# MCU025A_AltRouting_Misc.net
KiCad netlist of a schematic drawn in Altium Designer
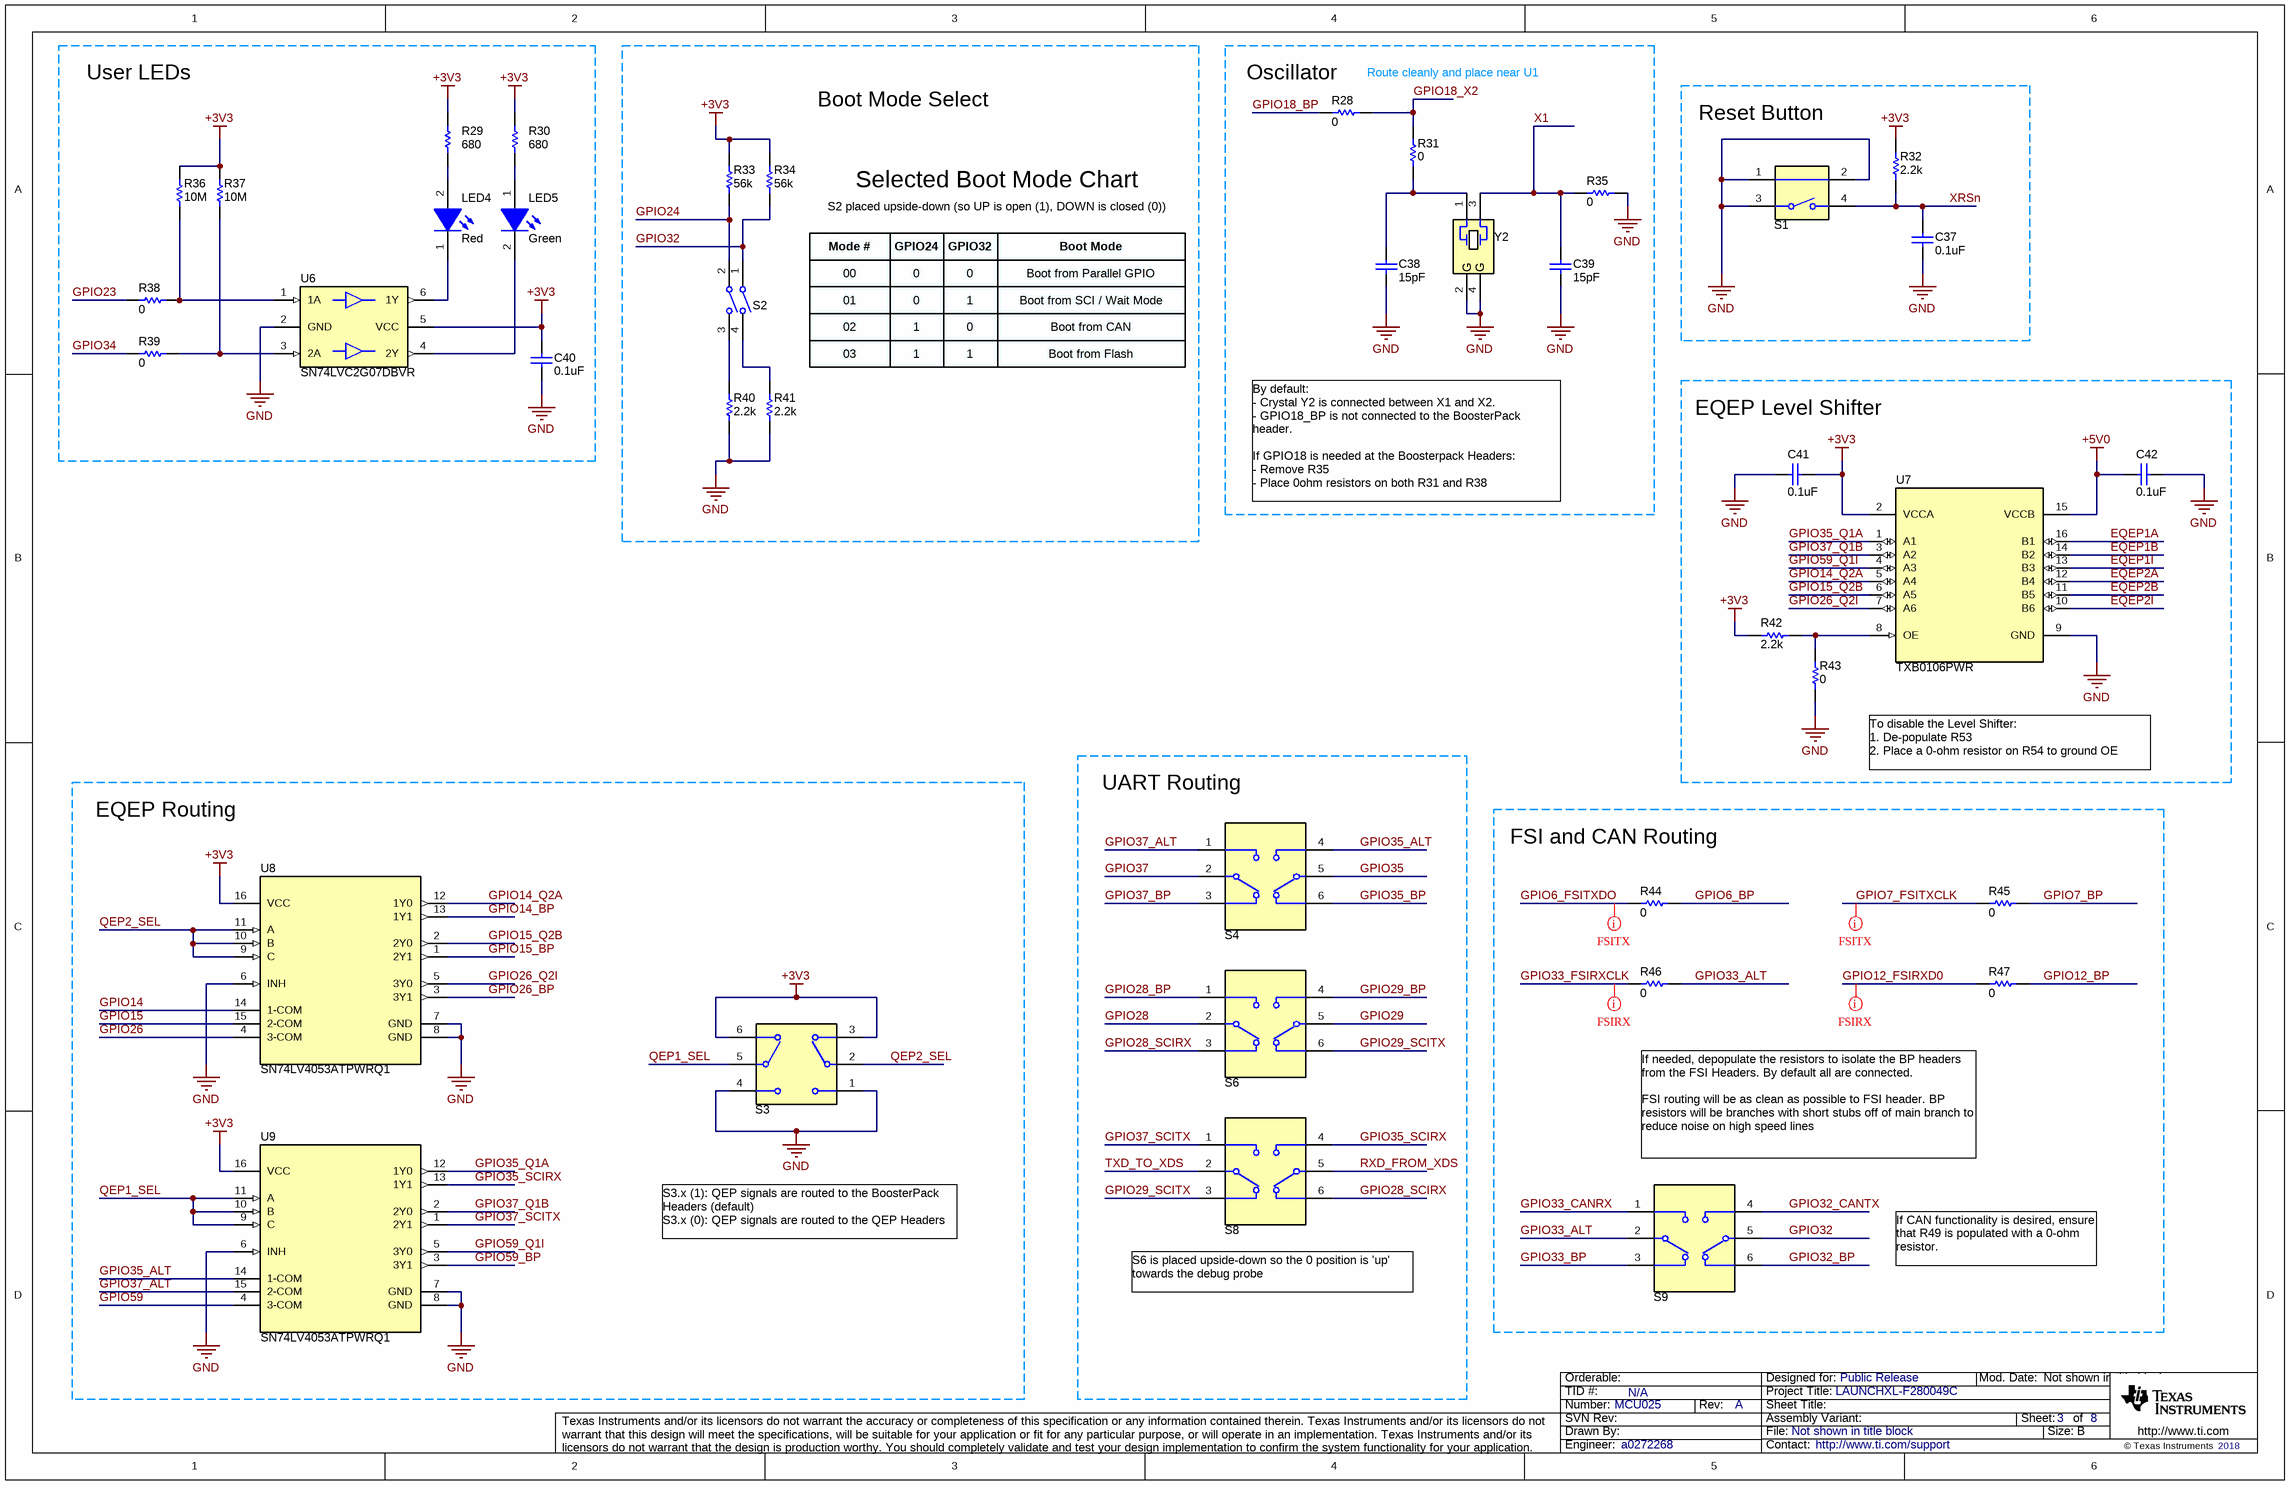
[diagram p0: MCU025A_AltRouting_Misc.SchDoc]

(export (version "E")
  (design (tool "Eeschema 10.0.6"))
  (components
    (comp (ref "C37")
      (value "GRM155R71A104KA01D")
      (footprint "0402")
      (description "CAP, CERM, 0.1 uF, 10 V, +/- 10%, X7R, 0402")
      (fields
        (field (name "VALUEDISPLAYED") "0.1uF")
        (field (name "MANUFACTURER") "MuRata")
        (field (name "PUBLISHER") "Texas Instruments")
      )
      (libsource (lib "Altium Vault - TI") (part "Capacitor"))
    )
    (comp (ref "C38")
      (value "GRM1555C1H150JA01D")
      (footprint "0402")
      (description "CAP, CERM, 15 pF, 50 V, +/- 5%, C0G/NP0, 0402")
      (fields
        (field (name "VALUEDISPLAYED") "15pF")
        (field (name "MANUFACTURER") "MuRata")
        (field (name "PUBLISHER") "Texas Instruments")
      )
      (libsource (lib "Altium Vault - TI") (part "Capacitor"))
    )
    (comp (ref "C39")
      (value "GRM1555C1H150JA01D")
      (footprint "0402")
      (description "CAP, CERM, 15 pF, 50 V, +/- 5%, C0G/NP0, 0402")
      (fields
        (field (name "VALUEDISPLAYED") "15pF")
        (field (name "MANUFACTURER") "MuRata")
        (field (name "PUBLISHER") "Texas Instruments")
      )
      (libsource (lib "Altium Vault - TI") (part "Capacitor"))
    )
    (comp (ref "C40")
      (value "GRM155R71A104KA01D")
      (footprint "0402")
      (description "CAP, CERM, 0.1 uF, 10 V, +/- 10%, X7R, 0402")
      (fields
        (field (name "VALUEDISPLAYED") "0.1uF")
        (field (name "MANUFACTURER") "MuRata")
        (field (name "PUBLISHER") "Texas Instruments")
      )
      (libsource (lib "Altium Vault - TI") (part "Capacitor"))
    )
    (comp (ref "C41")
      (value "GRM155R71A104KA01D")
      (footprint "0402")
      (description "CAP, CERM, 0.1 uF, 10 V, +/- 10%, X7R, 0402")
      (fields
        (field (name "VALUEDISPLAYED") "0.1uF")
        (field (name "MANUFACTURER") "MuRata")
        (field (name "PUBLISHER") "Texas Instruments")
      )
      (libsource (lib "Altium Vault - TI") (part "Capacitor"))
    )
    (comp (ref "C42")
      (value "GRM155R71A104KA01D")
      (footprint "0402")
      (description "CAP, CERM, 0.1 uF, 10 V, +/- 10%, X7R, 0402")
      (fields
        (field (name "VALUEDISPLAYED") "0.1uF")
        (field (name "MANUFACTURER") "MuRata")
        (field (name "PUBLISHER") "Texas Instruments")
      )
      (libsource (lib "Altium Vault - TI") (part "Capacitor"))
    )
    (comp (ref "LED4")
      (value "Red")
      (footprint "WL-SMCW_RED_0805")
      (description "LED, Red, SMD")
      (fields
        (field (name "MANUFACTURER") "Wurth Elektronik")
        (field (name "PARTNUMBER") "150080SS75000")
        (field (name "PUBLISHER") "Texas Instruments")
      )
      (libsource (lib "Altium Vault - TI") (part "LED_A2_K1"))
    )
    (comp (ref "LED5")
      (value "Green")
      (footprint "LED_LTST-C171")
      (description "LED, Green, SMD")
      (fields
        (field (name "MANUFACTURER") "Lite-On")
        (field (name "PARTNUMBER") "LTST-C171GKT")
        (field (name "PUBLISHER") "Texas Instruments")
      )
      (libsource (lib "Altium Vault - TI") (part "LED"))
    )
    (comp (ref "R28")
      (value "CRCW06030000Z0EA")
      (footprint "0603")
      (description "RES, 0, 5%, 0.1 W, AEC-Q200 Grade 0, 0603")
      (fields (field (name "VALUEDISPLAYED") "0") (field (name "MANUFACTURER") "Vishay-Dale"))
      (libsource (lib "Altium Vault - TI") (part "Resistor"))
    )
    (comp (ref "R29")
      (value "CRCW0402680RJNED")
      (footprint "0402")
      (description "RES, 680, 5%, 0.063 W, AEC-Q200 Grade 0, 0402")
      (fields (field (name "MANUFACTURER") "Vishay-Dale") (field (name "VALUEDISPLAYED") "680"))
      (libsource (lib "Altium Vault - TI") (part "CMP-0026962-3"))
    )
    (comp (ref "R30")
      (value "CRCW0402680RJNED")
      (footprint "0402")
      (description "RES, 680, 5%, 0.063 W, AEC-Q200 Grade 0, 0402")
      (fields (field (name "MANUFACTURER") "Vishay-Dale") (field (name "VALUEDISPLAYED") "680"))
      (libsource (lib "Altium Vault - TI") (part "CMP-0026962-3"))
    )
    (comp (ref "R31")
      (value "CRCW06030000Z0EA")
      (footprint "0603")
      (description "RES, 0, 5%, 0.1 W, AEC-Q200 Grade 0, 0603")
      (fields (field (name "VALUEDISPLAYED") "0") (field (name "MANUFACTURER") "Vishay-Dale"))
      (libsource (lib "Altium Vault - TI") (part "Resistor"))
    )
    (comp (ref "R32")
      (value "CRCW04022K20JNED")
      (footprint "0402")
      (description "RES, 2.2 k, 5%, 0.063 W, AEC-Q200 Grade 0, 0402")
      (fields (field (name "VALUEDISPLAYED") "2.2k") (field (name "MANUFACTURER") "Vishay-Dale"))
      (libsource (lib "Altium Vault - TI") (part "Resistor"))
    )
    (comp (ref "R33")
      (value "CRCW040256K0JNED")
      (footprint "0402")
      (description "RES, 56 k, 5%, 0.063 W, AEC-Q200 Grade 0, 0402")
      (fields (field (name "VALUEDISPLAYED") "56k") (field (name "MANUFACTURER") "Vishay-Dale"))
      (libsource (lib "Altium Vault - TI") (part "Resistor"))
    )
    (comp (ref "R34")
      (value "CRCW040256K0JNED")
      (footprint "0402")
      (description "RES, 56 k, 5%, 0.063 W, AEC-Q200 Grade 0, 0402")
      (fields (field (name "VALUEDISPLAYED") "56k") (field (name "MANUFACTURER") "Vishay-Dale"))
      (libsource (lib "Altium Vault - TI") (part "Resistor"))
    )
    (comp (ref "R35")
      (value "CRCW06030000Z0EA")
      (footprint "0603")
      (description "RES, 0, 5%, 0.1 W, AEC-Q200 Grade 0, 0603")
      (fields (field (name "VALUEDISPLAYED") "0") (field (name "MANUFACTURER") "Vishay-Dale"))
      (libsource (lib "Altium Vault - TI") (part "Resistor"))
    )
    (comp (ref "R36")
      (value "CRCW040210M0JNED")
      (footprint "0402")
      (description "RES, 10 M, 5%, 0.063 W, AEC-Q200 Grade 0, 0402")
      (fields (field (name "VALUEDISPLAYED") "10M") (field (name "MANUFACTURER") "Vishay-Dale"))
      (libsource (lib "Altium Vault - TI") (part "Resistor"))
    )
    (comp (ref "R37")
      (value "CRCW040210M0JNED")
      (footprint "0402")
      (description "RES, 10 M, 5%, 0.063 W, AEC-Q200 Grade 0, 0402")
      (fields (field (name "VALUEDISPLAYED") "10M") (field (name "MANUFACTURER") "Vishay-Dale"))
      (libsource (lib "Altium Vault - TI") (part "Resistor"))
    )
    (comp (ref "R38")
      (value "CRCW06030000Z0EA")
      (footprint "0603")
      (description "RES, 0, 5%, 0.1 W, AEC-Q200 Grade 0, 0603")
      (fields (field (name "VALUEDISPLAYED") "0") (field (name "MANUFACTURER") "Vishay-Dale"))
      (libsource (lib "Altium Vault - TI") (part "Resistor"))
    )
    (comp (ref "R39")
      (value "CRCW06030000Z0EA")
      (footprint "0603")
      (description "RES, 0, 5%, 0.1 W, AEC-Q200 Grade 0, 0603")
      (fields (field (name "VALUEDISPLAYED") "0") (field (name "MANUFACTURER") "Vishay-Dale"))
      (libsource (lib "Altium Vault - TI") (part "Resistor"))
    )
    (comp (ref "R40")
      (value "CRCW04022K20JNED")
      (footprint "0402")
      (description "RES, 2.2 k, 5%, 0.063 W, AEC-Q200 Grade 0, 0402")
      (fields (field (name "VALUEDISPLAYED") "2.2k") (field (name "MANUFACTURER") "Vishay-Dale"))
      (libsource (lib "Altium Vault - TI") (part "Resistor"))
    )
    (comp (ref "R41")
      (value "CRCW04022K20JNED")
      (footprint "0402")
      (description "RES, 2.2 k, 5%, 0.063 W, AEC-Q200 Grade 0, 0402")
      (fields (field (name "VALUEDISPLAYED") "2.2k") (field (name "MANUFACTURER") "Vishay-Dale"))
      (libsource (lib "Altium Vault - TI") (part "Resistor"))
    )
    (comp (ref "R42")
      (value "CRCW06032K20JNEA")
      (footprint "0603")
      (description "RES, 2.2 k, 5%, 0.1 W, AEC-Q200 Grade 0, 0603")
      (fields (field (name "VALUEDISPLAYED") "2.2k") (field (name "MANUFACTURER") "Vishay-Dale"))
      (libsource (lib "Altium Vault - TI") (part "Resistor"))
    )
    (comp (ref "R43")
      (value "CRCW06030000Z0EA")
      (footprint "0603")
      (description "RES, 0, 5%, 0.1 W, AEC-Q200 Grade 0, 0603")
      (fields (field (name "VALUEDISPLAYED") "0") (field (name "MANUFACTURER") "Vishay-Dale"))
      (libsource (lib "Altium Vault - TI") (part "Resistor"))
    )
    (comp (ref "R44")
      (value "CRCW06030000Z0EA")
      (footprint "0603")
      (description "RES, 0, 5%, 0.1 W, AEC-Q200 Grade 0, 0603")
      (fields (field (name "VALUEDISPLAYED") "0") (field (name "MANUFACTURER") "Vishay-Dale"))
      (libsource (lib "Altium Vault - TI") (part "Resistor"))
    )
    (comp (ref "R45")
      (value "CRCW06030000Z0EA")
      (footprint "0603")
      (description "RES, 0, 5%, 0.1 W, AEC-Q200 Grade 0, 0603")
      (fields (field (name "VALUEDISPLAYED") "0") (field (name "MANUFACTURER") "Vishay-Dale"))
      (libsource (lib "Altium Vault - TI") (part "Resistor"))
    )
    (comp (ref "R46")
      (value "CRCW06030000Z0EA")
      (footprint "0603")
      (description "RES, 0, 5%, 0.1 W, AEC-Q200 Grade 0, 0603")
      (fields (field (name "VALUEDISPLAYED") "0") (field (name "MANUFACTURER") "Vishay-Dale"))
      (libsource (lib "Altium Vault - TI") (part "Resistor"))
    )
    (comp (ref "R47")
      (value "CRCW06030000Z0EA")
      (footprint "0603")
      (description "RES, 0, 5%, 0.1 W, AEC-Q200 Grade 0, 0603")
      (fields (field (name "VALUEDISPLAYED") "0") (field (name "MANUFACTURER") "Vishay-Dale"))
      (libsource (lib "Altium Vault - TI") (part "Resistor"))
    )
    (comp (ref "S1")
      (value "1188E-1K2-V-TR")
      (footprint "SW_1188E")
      (description "Switch, SPST, 0.05 A, 12 VDC, SMD")
      (fields (field (name "MANUFACTURER") "Diptronics") (field (name "PUBLISHER") "Texas Instruments"))
      (libsource (lib "Altium Vault - TI") (part "SW_1188E"))
    )
    (comp (ref "S2")
      (value "218-2LPST")
      (footprint "SW_218-2LP")
      (description "Switch, SPST, 2 Pos, 25mA, 24VDC, SMD")
      (fields
        (field (name "MANUFACTURER") "CTS Electrocomponents")
        (field (name "PUBLISHER") "Texas Instruments")
      )
      (libsource (lib "Altium Vault - TI") (part "SW_2SPST"))
    )
    (comp (ref "S3")
      (value "CAS-D20TA")
      (footprint "SW_CAS-D20TA")
      (description "Switch, Dual SPDT,  2 Pos, 0.1A, 6VDC, SMD")
      (fields
        (field (name "MANUFACTURER") "Copal Electronics")
        (field (name "PUBLISHER") "Texas Instruments")
      )
      (libsource (lib "Altium Vault - TI") (part "SW_SPDT_CAS-D20TA"))
    )
    (comp (ref "S4")
      (value "CAS-220TA")
      (footprint "SW_CAS-220TA")
      (description "SLIDE SWITCH DPDT  .1A, SMT")
      (fields
        (field (name "MANUFACTURER") "Copal Electronics")
        (field (name "PUBLISHER") "Texas Instruments")
      )
      (libsource (lib "Altium Vault - TI") (part "SW_CAS-220TA"))
    )
    (comp (ref "S6")
      (value "CAS-220TA")
      (footprint "SW_CAS-220TA")
      (description "SLIDE SWITCH DPDT  .1A, SMT")
      (fields
        (field (name "MANUFACTURER") "Copal Electronics")
        (field (name "PUBLISHER") "Texas Instruments")
      )
      (libsource (lib "Altium Vault - TI") (part "SW_CAS-220TA"))
    )
    (comp (ref "S8")
      (value "CAS-220TA")
      (footprint "SW_CAS-220TA")
      (description "SLIDE SWITCH DPDT  .1A, SMT")
      (fields
        (field (name "MANUFACTURER") "Copal Electronics")
        (field (name "PUBLISHER") "Texas Instruments")
      )
      (libsource (lib "Altium Vault - TI") (part "SW_CAS-220TA"))
    )
    (comp (ref "S9")
      (value "CAS-220TA")
      (footprint "SW_CAS-220TA")
      (description "SLIDE SWITCH DPDT  .1A, SMT")
      (fields
        (field (name "MANUFACTURER") "Copal Electronics")
        (field (name "PUBLISHER") "Texas Instruments")
      )
      (libsource (lib "Altium Vault - TI") (part "SW_CAS-220TA"))
    )
    (comp (ref "U6")
      (value "SN74LVC2G07DBVR")
      (footprint "DBV0006A_N")
      (description "Dual Buffer/Driver with Open-Drain Output, DBV0006A, LARGE T&R")
      (fields
        (field (name "GENERIC PART NUMBER") "SN74LVC2G07")
        (field (name "MANUFACTURER") "Texas Instruments")
      )
      (libsource (lib "Altium Vault - TI") (part "CMP-0051789-2"))
    )
    (comp (ref "U7")
      (value "TXB0106PWR")
      (footprint "PW0016A_N")
      (fields
        (field (name "MANUFACTURER") "Texas Instruments")
        (field (name "PUBLISHER") "Texas Instruments")
      )
      (libsource (lib "Altium Vault - TI") (part "TXB0106PW"))
    )
    (comp (ref "U8")
      (value "SN74LV4053ATPWRQ1")
      (footprint "PW0016A_L")
      (description "TRIPLE 2-CHANNEL ANALOG MULTIPLEXER/DEMULTIPLEXER, PW0016A (TSSOP-16)")
      (fields
        (field (name "PARTNUMBER") "SN74LV4053ATPWRQ1")
        (field (name "MANUFACTURER") "Texas Instruments")
        (field (name "PUBLISHER") "Texas Instruments")
      )
      (libsource (lib "Altium Vault - TI") (part "SN74LV4053A-Q1"))
    )
    (comp (ref "U9")
      (value "SN74LV4053ATPWRQ1")
      (footprint "PW0016A_L")
      (description "TRIPLE 2-CHANNEL ANALOG MULTIPLEXER/DEMULTIPLEXER, PW0016A (TSSOP-16)")
      (fields
        (field (name "PARTNUMBER") "SN74LV4053ATPWRQ1")
        (field (name "MANUFACTURER") "Texas Instruments")
        (field (name "PUBLISHER") "Texas Instruments")
      )
      (libsource (lib "Altium Vault - TI") (part "SN74LV4053A-Q1"))
    )
    (comp (ref "Y2")
      (value "ECS-200-18-30B-AGN-TR")
      (footprint "ECS_ECX-53B")
      (description "Crystal, 20 MHz, 25 ppm, 18, SMD")
      (fields (field (name "MANUFACTURER") "ECS Inc."))
      (libsource (lib "Altium Vault - TI") (part "CMP-0080365-1"))
    )
  )
  (nets
    (net (code "1") (name "+3V3") (class "Default")
      (node (ref "C40") (pin "2") (pinfunction "2_2") (pintype "passive"))
      (node (ref "C41") (pin "1") (pinfunction "1_1") (pintype "passive"))
      (node (ref "R29") (pin "2") (pinfunction "2_2") (pintype "passive"))
      (node (ref "R30") (pin "2") (pinfunction "2_2") (pintype "passive"))
      (node (ref "R32") (pin "2") (pinfunction "2_2") (pintype "passive"))
      (node (ref "R33") (pin "2") (pinfunction "2_2") (pintype "passive"))
      (node (ref "R34") (pin "2") (pinfunction "2_2") (pintype "passive"))
      (node (ref "R36") (pin "2") (pinfunction "2_2") (pintype "passive"))
      (node (ref "R37") (pin "2") (pinfunction "2_2") (pintype "passive"))
      (node (ref "R42") (pin "1") (pinfunction "1_1") (pintype "passive"))
      (node (ref "S3") (pin "3") (pinfunction "3_3") (pintype "passive"))
      (node (ref "S3") (pin "6") (pinfunction "6_6") (pintype "passive"))
      (node (ref "U6") (pin "5") (pinfunction "VCC_5") (pintype "power_in"))
      (node (ref "U7") (pin "2") (pinfunction "VCCA_2") (pintype "power_in"))
      (node (ref "U8") (pin "16") (pinfunction "VCC_16") (pintype "power_in"))
      (node (ref "U9") (pin "16") (pinfunction "VCC_16") (pintype "power_in"))
    )
    (net (code "2") (name "+5V0") (class "Default")
      (node (ref "C42") (pin "2") (pinfunction "2_2") (pintype "passive"))
      (node (ref "U7") (pin "15") (pinfunction "VCCB_15") (pintype "power_in"))
    )
    (net (code "3") (name "/EQEP1A") (class "Default")
      (node (ref "U7") (pin "16") (pinfunction "B1_16") (pintype "bidirectional"))
    )
    (net (code "4") (name "/EQEP1B") (class "Default")
      (node (ref "U7") (pin "14") (pinfunction "B2_14") (pintype "bidirectional"))
    )
    (net (code "5") (name "/EQEP1I") (class "Default")
      (node (ref "U7") (pin "13") (pinfunction "B3_13") (pintype "bidirectional"))
    )
    (net (code "6") (name "/EQEP2A") (class "Default")
      (node (ref "U7") (pin "12") (pinfunction "B4_12") (pintype "bidirectional"))
    )
    (net (code "7") (name "/EQEP2B") (class "Default")
      (node (ref "U7") (pin "11") (pinfunction "B5_11") (pintype "bidirectional"))
    )
    (net (code "8") (name "/EQEP2I") (class "Default")
      (node (ref "U7") (pin "10") (pinfunction "B6_10") (pintype "bidirectional"))
    )
    (net (code "9") (name "/GPIO6_BP") (class "Default")
      (node (ref "R44") (pin "2") (pinfunction "2_2") (pintype "passive"))
    )
    (net (code "10") (name "/GPIO6_FSITXDO") (class "Default")
      (node (ref "R44") (pin "1") (pinfunction "1_1") (pintype "passive"))
    )
    (net (code "11") (name "/GPIO7_BP") (class "Default")
      (node (ref "R45") (pin "2") (pinfunction "2_2") (pintype "passive"))
    )
    (net (code "12") (name "/GPIO7_FSITXCLK") (class "Default")
      (node (ref "R45") (pin "1") (pinfunction "1_1") (pintype "passive"))
    )
    (net (code "13") (name "/GPIO12_BP") (class "Default")
      (node (ref "R47") (pin "2") (pinfunction "2_2") (pintype "passive"))
    )
    (net (code "14") (name "/GPIO12_FSIRXD0") (class "Default")
      (node (ref "R47") (pin "1") (pinfunction "1_1") (pintype "passive"))
    )
    (net (code "15") (name "/GPIO14") (class "Default")
      (node (ref "U8") (pin "14") (pinfunction "1-COM_14") (pintype "passive"))
    )
    (net (code "16") (name "/GPIO14_BP") (class "Default")
      (node (ref "U8") (pin "13") (pinfunction "1Y1_13") (pintype "output"))
    )
    (net (code "17") (name "/GPIO14_Q2A") (class "Default")
      (node (ref "U7") (pin "5") (pinfunction "A4_5") (pintype "bidirectional"))
      (node (ref "U8") (pin "12") (pinfunction "1Y0_12") (pintype "output"))
    )
    (net (code "18") (name "/GPIO15") (class "Default")
      (node (ref "U8") (pin "15") (pinfunction "2-COM_15") (pintype "passive"))
    )
    (net (code "19") (name "/GPIO15_BP") (class "Default")
      (node (ref "U8") (pin "1") (pinfunction "2Y1_1") (pintype "output"))
    )
    (net (code "20") (name "/GPIO15_Q2B") (class "Default")
      (node (ref "U7") (pin "6") (pinfunction "A5_6") (pintype "bidirectional"))
      (node (ref "U8") (pin "2") (pinfunction "2Y0_2") (pintype "output"))
    )
    (net (code "21") (name "/GPIO18_BP") (class "Default")
      (node (ref "R28") (pin "1") (pinfunction "1_1") (pintype "passive"))
    )
    (net (code "22") (name "/GPIO18_X2") (class "Default")
      (node (ref "R28") (pin "2") (pinfunction "2_2") (pintype "passive"))
      (node (ref "R31") (pin "2") (pinfunction "2_2") (pintype "passive"))
    )
    (net (code "23") (name "/GPIO23") (class "Default")
      (node (ref "R38") (pin "1") (pinfunction "1_1") (pintype "passive"))
    )
    (net (code "24") (name "/GPIO24") (class "Default")
      (node (ref "R33") (pin "1") (pinfunction "1_1") (pintype "passive"))
      (node (ref "S2") (pin "2") (pinfunction "2_2") (pintype "passive"))
    )
    (net (code "25") (name "/GPIO26") (class "Default")
      (node (ref "U8") (pin "4") (pinfunction "3-COM_4") (pintype "passive"))
    )
    (net (code "26") (name "/GPIO26_BP") (class "Default")
      (node (ref "U8") (pin "3") (pinfunction "3Y1_3") (pintype "output"))
    )
    (net (code "27") (name "/GPIO26_Q2I") (class "Default")
      (node (ref "U7") (pin "7") (pinfunction "A6_7") (pintype "bidirectional"))
      (node (ref "U8") (pin "5") (pinfunction "3Y0_5") (pintype "output"))
    )
    (net (code "28") (name "/GPIO28") (class "Default")
      (node (ref "S6") (pin "2") (pinfunction "2_2") (pintype "passive"))
    )
    (net (code "29") (name "/GPIO28_BP") (class "Default")
      (node (ref "S6") (pin "1") (pinfunction "1_1") (pintype "passive"))
    )
    (net (code "30") (name "/GPIO28_SCIRX") (class "Default")
      (node (ref "S6") (pin "3") (pinfunction "3_3") (pintype "passive"))
      (node (ref "S8") (pin "6") (pinfunction "6_6") (pintype "passive"))
    )
    (net (code "31") (name "/GPIO29") (class "Default")
      (node (ref "S6") (pin "5") (pinfunction "5_5") (pintype "passive"))
    )
    (net (code "32") (name "/GPIO29_BP") (class "Default")
      (node (ref "S6") (pin "4") (pinfunction "4_4") (pintype "passive"))
    )
    (net (code "33") (name "/GPIO29_SCITX") (class "Default")
      (node (ref "S6") (pin "6") (pinfunction "6_6") (pintype "passive"))
      (node (ref "S8") (pin "3") (pinfunction "3_3") (pintype "passive"))
    )
    (net (code "34") (name "/GPIO32") (class "Default")
      (node (ref "R34") (pin "1") (pinfunction "1_1") (pintype "passive"))
      (node (ref "S2") (pin "1") (pinfunction "1_1") (pintype "passive"))
      (node (ref "S9") (pin "5") (pinfunction "5_5") (pintype "passive"))
    )
    (net (code "35") (name "/GPIO32_BP") (class "Default")
      (node (ref "S9") (pin "6") (pinfunction "6_6") (pintype "passive"))
    )
    (net (code "36") (name "/GPIO32_CANTX") (class "Default")
      (node (ref "S9") (pin "4") (pinfunction "4_4") (pintype "passive"))
    )
    (net (code "37") (name "/GPIO33_ALT") (class "Default")
      (node (ref "R46") (pin "2") (pinfunction "2_2") (pintype "passive"))
      (node (ref "S9") (pin "2") (pinfunction "2_2") (pintype "passive"))
    )
    (net (code "38") (name "/GPIO33_BP") (class "Default")
      (node (ref "S9") (pin "3") (pinfunction "3_3") (pintype "passive"))
    )
    (net (code "39") (name "/GPIO33_CANRX") (class "Default")
      (node (ref "S9") (pin "1") (pinfunction "1_1") (pintype "passive"))
    )
    (net (code "40") (name "/GPIO33_FSIRXCLK") (class "Default")
      (node (ref "R46") (pin "1") (pinfunction "1_1") (pintype "passive"))
    )
    (net (code "41") (name "/GPIO34") (class "Default")
      (node (ref "R39") (pin "1") (pinfunction "1_1") (pintype "passive"))
    )
    (net (code "42") (name "/GPIO35") (class "Default")
      (node (ref "S4") (pin "5") (pinfunction "5_5") (pintype "passive"))
    )
    (net (code "43") (name "/GPIO35_ALT") (class "Default")
      (node (ref "S4") (pin "4") (pinfunction "4_4") (pintype "passive"))
      (node (ref "U9") (pin "14") (pinfunction "1-COM_14") (pintype "passive"))
    )
    (net (code "44") (name "/GPIO35_BP") (class "Default")
      (node (ref "S4") (pin "6") (pinfunction "6_6") (pintype "passive"))
    )
    (net (code "45") (name "/GPIO35_Q1A") (class "Default")
      (node (ref "U7") (pin "1") (pinfunction "A1_1") (pintype "bidirectional"))
      (node (ref "U9") (pin "12") (pinfunction "1Y0_12") (pintype "output"))
    )
    (net (code "46") (name "/GPIO35_SCIRX") (class "Default")
      (node (ref "S8") (pin "4") (pinfunction "4_4") (pintype "passive"))
      (node (ref "U9") (pin "13") (pinfunction "1Y1_13") (pintype "output"))
    )
    (net (code "47") (name "/GPIO37") (class "Default")
      (node (ref "S4") (pin "2") (pinfunction "2_2") (pintype "passive"))
    )
    (net (code "48") (name "/GPIO37_ALT") (class "Default")
      (node (ref "S4") (pin "1") (pinfunction "1_1") (pintype "passive"))
      (node (ref "U9") (pin "15") (pinfunction "2-COM_15") (pintype "passive"))
    )
    (net (code "49") (name "/GPIO37_BP") (class "Default")
      (node (ref "S4") (pin "3") (pinfunction "3_3") (pintype "passive"))
    )
    (net (code "50") (name "/GPIO37_Q1B") (class "Default")
      (node (ref "U7") (pin "3") (pinfunction "A2_3") (pintype "bidirectional"))
      (node (ref "U9") (pin "2") (pinfunction "2Y0_2") (pintype "output"))
    )
    (net (code "51") (name "/GPIO37_SCITX") (class "Default")
      (node (ref "S8") (pin "1") (pinfunction "1_1") (pintype "passive"))
      (node (ref "U9") (pin "1") (pinfunction "2Y1_1") (pintype "output"))
    )
    (net (code "52") (name "/GPIO59") (class "Default")
      (node (ref "U9") (pin "4") (pinfunction "3-COM_4") (pintype "passive"))
    )
    (net (code "53") (name "/GPIO59_BP") (class "Default")
      (node (ref "U9") (pin "3") (pinfunction "3Y1_3") (pintype "output"))
    )
    (net (code "54") (name "/GPIO59_Q1I") (class "Default")
      (node (ref "U7") (pin "4") (pinfunction "A3_4") (pintype "bidirectional"))
      (node (ref "U9") (pin "5") (pinfunction "3Y0_5") (pintype "output"))
    )
    (net (code "55") (name "/QEP1_SEL") (class "Default")
      (node (ref "S3") (pin "5") (pinfunction "C_5") (pintype "passive"))
      (node (ref "U9") (pin "10") (pinfunction "B_10") (pintype "input"))
      (node (ref "U9") (pin "11") (pinfunction "A_11") (pintype "input"))
      (node (ref "U9") (pin "9") (pinfunction "C_9") (pintype "input"))
    )
    (net (code "56") (name "/QEP2_SEL") (class "Default")
      (node (ref "S3") (pin "2") (pinfunction "C_2") (pintype "passive"))
      (node (ref "U8") (pin "10") (pinfunction "B_10") (pintype "input"))
      (node (ref "U8") (pin "11") (pinfunction "A_11") (pintype "input"))
      (node (ref "U8") (pin "9") (pinfunction "C_9") (pintype "input"))
    )
    (net (code "57") (name "/RXD_FROM_XDS") (class "Default")
      (node (ref "S8") (pin "5") (pinfunction "5_5") (pintype "passive"))
    )
    (net (code "58") (name "/TXD_TO_XDS") (class "Default")
      (node (ref "S8") (pin "2") (pinfunction "2_2") (pintype "passive"))
    )
    (net (code "59") (name "/X1") (class "Default")
      (node (ref "C39") (pin "1") (pinfunction "1_1") (pintype "passive"))
      (node (ref "R35") (pin "1") (pinfunction "1_1") (pintype "passive"))
      (node (ref "Y2") (pin "3") (pinfunction "3_3") (pintype "passive"))
    )
    (net (code "60") (name "/XRSn") (class "Default")
      (node (ref "C37") (pin "2") (pinfunction "2_2") (pintype "passive"))
      (node (ref "R32") (pin "1") (pinfunction "1_1") (pintype "passive"))
      (node (ref "S1") (pin "4") (pinfunction "4_4") (pintype "passive"))
    )
    (net (code "61") (name "GND") (class "Default")
      (node (ref "C37") (pin "1") (pinfunction "1_1") (pintype "passive"))
      (node (ref "C38") (pin "2") (pinfunction "2_2") (pintype "passive"))
      (node (ref "C39") (pin "2") (pinfunction "2_2") (pintype "passive"))
      (node (ref "C40") (pin "1") (pinfunction "1_1") (pintype "passive"))
      (node (ref "C41") (pin "2") (pinfunction "2_2") (pintype "passive"))
      (node (ref "C42") (pin "1") (pinfunction "1_1") (pintype "passive"))
      (node (ref "R35") (pin "2") (pinfunction "2_2") (pintype "passive"))
      (node (ref "R40") (pin "1") (pinfunction "1_1") (pintype "passive"))
      (node (ref "R41") (pin "1") (pinfunction "1_1") (pintype "passive"))
      (node (ref "R43") (pin "1") (pinfunction "1_1") (pintype "passive"))
      (node (ref "S1") (pin "1") (pinfunction "1_1") (pintype "passive"))
      (node (ref "S1") (pin "2") (pinfunction "2_2") (pintype "passive"))
      (node (ref "S1") (pin "3") (pinfunction "3_3") (pintype "passive"))
      (node (ref "S3") (pin "1") (pinfunction "1_1") (pintype "passive"))
      (node (ref "S3") (pin "4") (pinfunction "4_4") (pintype "passive"))
      (node (ref "U6") (pin "2") (pinfunction "GND_2") (pintype "power_in"))
      (node (ref "U7") (pin "9") (pinfunction "GND_9") (pintype "power_in"))
      (node (ref "U8") (pin "6") (pinfunction "INH_6") (pintype "input"))
      (node (ref "U8") (pin "7") (pinfunction "GND_7") (pintype "power_in"))
      (node (ref "U8") (pin "8") (pinfunction "GND_8") (pintype "power_in"))
      (node (ref "U9") (pin "6") (pinfunction "INH_6") (pintype "input"))
      (node (ref "U9") (pin "7") (pinfunction "GND_7") (pintype "power_in"))
      (node (ref "U9") (pin "8") (pinfunction "GND_8") (pintype "power_in"))
      (node (ref "Y2") (pin "2") (pinfunction "GND_2") (pintype "power_in"))
      (node (ref "Y2") (pin "4") (pinfunction "GND_4") (pintype "power_in"))
    )
    (net (code "62") (name "Net-(C38-Pad1)") (class "Default")
      (node (ref "C38") (pin "1") (pinfunction "1_1") (pintype "passive"))
      (node (ref "R31") (pin "1") (pinfunction "1_1") (pintype "passive"))
      (node (ref "Y2") (pin "1") (pinfunction "1_1") (pintype "passive"))
    )
    (net (code "63") (name "Net-(LED4-A)") (class "Default")
      (node (ref "LED4") (pin "2") (pinfunction "A_2") (pintype "passive"))
      (node (ref "R29") (pin "1") (pinfunction "1_1") (pintype "passive"))
    )
    (net (code "64") (name "Net-(LED4-K)") (class "Default")
      (node (ref "LED4") (pin "1") (pinfunction "K_1") (pintype "passive"))
      (node (ref "U6") (pin "6") (pinfunction "1Y_6") (pintype "output"))
    )
    (net (code "65") (name "Net-(LED5-A)") (class "Default")
      (node (ref "LED5") (pin "1") (pinfunction "A_1") (pintype "passive"))
      (node (ref "R30") (pin "1") (pinfunction "1_1") (pintype "passive"))
    )
    (net (code "66") (name "Net-(LED5-K)") (class "Default")
      (node (ref "LED5") (pin "2") (pinfunction "K_2") (pintype "passive"))
      (node (ref "U6") (pin "4") (pinfunction "2Y_4") (pintype "output"))
    )
    (net (code "67") (name "Net-(R40-Pad2)") (class "Default")
      (node (ref "R40") (pin "2") (pinfunction "2_2") (pintype "passive"))
      (node (ref "S2") (pin "3") (pinfunction "3_3") (pintype "passive"))
    )
    (net (code "68") (name "Net-(R41-Pad2)") (class "Default")
      (node (ref "R41") (pin "2") (pinfunction "2_2") (pintype "passive"))
      (node (ref "S2") (pin "4") (pinfunction "4_4") (pintype "passive"))
    )
    (net (code "69") (name "Net-(U6-1A)") (class "Default")
      (node (ref "R36") (pin "1") (pinfunction "1_1") (pintype "passive"))
      (node (ref "R38") (pin "2") (pinfunction "2_2") (pintype "passive"))
      (node (ref "U6") (pin "1") (pinfunction "1A_1") (pintype "input"))
    )
    (net (code "70") (name "Net-(U6-2A)") (class "Default")
      (node (ref "R37") (pin "1") (pinfunction "1_1") (pintype "passive"))
      (node (ref "R39") (pin "2") (pinfunction "2_2") (pintype "passive"))
      (node (ref "U6") (pin "3") (pinfunction "2A_3") (pintype "input"))
    )
    (net (code "71") (name "Net-(U7-OE)") (class "Default")
      (node (ref "R42") (pin "2") (pinfunction "2_2") (pintype "passive"))
      (node (ref "R43") (pin "2") (pinfunction "2_2") (pintype "passive"))
      (node (ref "U7") (pin "8") (pinfunction "OE_8") (pintype "input"))
    )
  )
)
